# Sheet1.net
KiCad netlist of a schematic drawn in Altium Designer
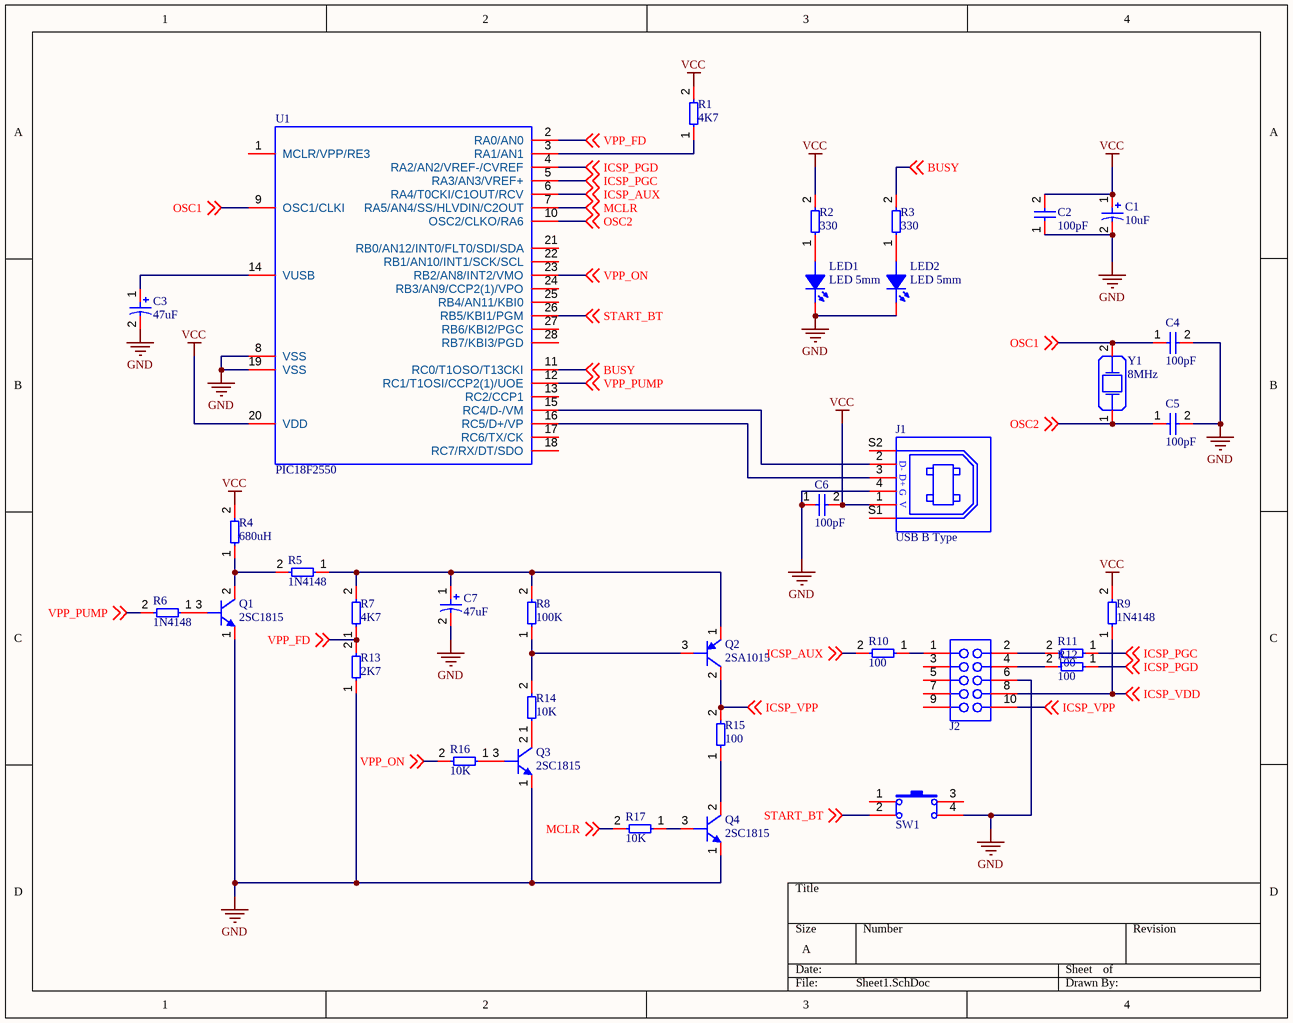
[diagram p0: Sheet1.SchDoc]

(export (version "E")
  (design (tool "Eeschema 10.0.6"))
  (components
    (comp (ref "C1")
      (value "10uF")
      (footprint "CAP_RAD_4mm")
      (libsource (lib "SMDLibrary") (part "Capacitor(Radian)"))
    )
    (comp (ref "C2")
      (value "100pF")
      (footprint "CAP_DISC_PITCH_2.54MM")
      (libsource (lib "SMDLibrary") (part "Capacitors(Disc)"))
    )
    (comp (ref "C3")
      (value "47uF")
      (footprint "CAP_RAD_4mm")
      (libsource (lib "SMDLibrary") (part "Capacitor(Radian)"))
    )
    (comp (ref "C4")
      (value "100pF")
      (footprint "CAP_DISC_PITCH_2.54MM")
      (libsource (lib "SMDLibrary") (part "Capacitors(Disc)"))
    )
    (comp (ref "C5")
      (value "100pF")
      (footprint "CAP_DISC_PITCH_2.54MM")
      (libsource (lib "SMDLibrary") (part "Capacitors(Disc)"))
    )
    (comp (ref "C6")
      (value "100pF")
      (footprint "CAP_DISC_PITCH_2.54MM")
      (libsource (lib "SMDLibrary") (part "Capacitors(Disc)"))
    )
    (comp (ref "C7")
      (value "47uF")
      (footprint "CAP_RAD_4mm")
      (libsource (lib "SMDLibrary") (part "Capacitor(Radian)"))
    )
    (comp (ref "J1")
      (value "USB B Type")
      (footprint "USB-B-TYPE")
      (libsource (lib "SMDLibrary") (part "USB B Type"))
    )
    (comp (ref "J2")
      (value "Header 5x2 TH Pitch 2.54mm")
      (footprint "Header 5x2 TH Pitch 2.54mm")
      (libsource (lib "SMDLibrary") (part "Header 5x2 TH Pitch 2.54mm"))
    )
    (comp (ref "LED1")
      (value "LED 5mm")
      (footprint "LED_5MM")
      (libsource (lib "SMDLibrary") (part "LED 5mm"))
    )
    (comp (ref "LED2")
      (value "LED 5mm")
      (footprint "LED_5MM")
      (libsource (lib "SMDLibrary") (part "LED 5mm"))
    )
    (comp (ref "Q1")
      (value "2SC1815")
      (footprint "TO-92")
      (libsource (lib "SMDLibrary") (part "2SC1815 (TO-92)"))
    )
    (comp (ref "Q2")
      (value "2SA1015")
      (footprint "TO-92")
      (libsource (lib "SMDLibrary") (part "2SA1015 (TO-92)"))
    )
    (comp (ref "Q3")
      (value "2SC1815")
      (footprint "TO-92")
      (libsource (lib "SMDLibrary") (part "2SC1815 (TO-92)"))
    )
    (comp (ref "Q4")
      (value "2SC1815")
      (footprint "TO-92")
      (libsource (lib "SMDLibrary") (part "2SC1815 (TO-92)"))
    )
    (comp (ref "R1")
      (value "4K7")
      (footprint "RES-0.25W-H-MF")
      (libsource (lib "SMDLibrary") (part "Resistors THD"))
    )
    (comp (ref "R2")
      (value "330")
      (footprint "RES-0.25W-H-MF")
      (libsource (lib "SMDLibrary") (part "Resistors THD"))
    )
    (comp (ref "R3")
      (value "330")
      (footprint "RES-0.25W-H-MF")
      (libsource (lib "SMDLibrary") (part "Resistors THD"))
    )
    (comp (ref "R4")
      (value "680uH")
      (footprint "RES-0.5W-HH-MF")
      (libsource (lib "SMDLibrary") (part "Resistors THD"))
    )
    (comp (ref "R5")
      (value "1N4148")
      (footprint "RES-0.25W-H-MF")
      (libsource (lib "") (part "Resistors THD_1"))
    )
    (comp (ref "R6")
      (value "1N4148")
      (footprint "RES-0.25W-H-MF")
      (libsource (lib "") (part "Resistors THD_1"))
    )
    (comp (ref "R7")
      (value "4K7")
      (footprint "RES-0.25W-H-MF")
      (libsource (lib "SMDLibrary") (part "Resistors THD"))
    )
    (comp (ref "R8")
      (value "100K")
      (footprint "RES-0.25W-H-MF")
      (libsource (lib "SMDLibrary") (part "Resistors THD"))
    )
    (comp (ref "R9")
      (value "1N4148")
      (footprint "RES-0.25W-H-MF")
      (libsource (lib "SMDLibrary") (part "Resistors THD"))
    )
    (comp (ref "R10")
      (value "100")
      (footprint "RES-0.25W-H-MF")
      (libsource (lib "") (part "Resistors THD_1"))
    )
    (comp (ref "R11")
      (value "100")
      (footprint "RES-0.25W-H-MF")
      (libsource (lib "") (part "Resistors THD_1"))
    )
    (comp (ref "R12")
      (value "100")
      (footprint "RES-0.25W-H-MF")
      (libsource (lib "") (part "Resistors THD_1"))
    )
    (comp (ref "R13")
      (value "2K7")
      (footprint "RES-0.25W-H-MF")
      (libsource (lib "SMDLibrary") (part "Resistors THD"))
    )
    (comp (ref "R14")
      (value "10K")
      (footprint "RES-0.25W-H-MF")
      (libsource (lib "SMDLibrary") (part "Resistors THD"))
    )
    (comp (ref "R15")
      (value "100")
      (footprint "RES-0.25W-H-MF")
      (libsource (lib "SMDLibrary") (part "Resistors THD"))
    )
    (comp (ref "R16")
      (value "10K")
      (footprint "RES-0.25W-H-MF")
      (libsource (lib "") (part "Resistors THD_1"))
    )
    (comp (ref "R17")
      (value "10K")
      (footprint "RES-0.25W-H-MF")
      (libsource (lib "") (part "Resistors THD_1"))
    )
    (comp (ref "SW1")
      (value "Button Hole")
      (footprint "BUTTON_HOLE_5.0mm")
      (libsource (lib "SMDLibrary") (part "Button Hole"))
    )
    (comp (ref "U1")
      (value "PIC18F2550")
      (footprint "DIP28_M04")
      (libsource (lib "SMDLibrary") (part "PIC18F2550"))
    )
    (comp (ref "Y1") (value "8MHz") (footprint "HC-49S") (libsource (lib "SMDLibrary") (part "Crystal")))
  )
  (nets
    (net (code "1") (name "BUSY") (class "Default")
      (node (ref "R3") (pin "2") (pinfunction "2_2") (pintype "passive"))
      (node (ref "U1") (pin "11") (pinfunction "RC0/T1OSO/T13CKI_11") (pintype "passive"))
    )
    (net (code "2") (name "GND") (class "Default")
      (node (ref "C1") (pin "2") (pinfunction "2_2") (pintype "passive"))
      (node (ref "C2") (pin "1") (pinfunction "1_1") (pintype "passive"))
      (node (ref "C3") (pin "2") (pinfunction "2_2") (pintype "passive"))
      (node (ref "C4") (pin "2") (pinfunction "2_2") (pintype "passive"))
      (node (ref "C5") (pin "2") (pinfunction "2_2") (pintype "passive"))
      (node (ref "C6") (pin "1") (pinfunction "1_1") (pintype "passive"))
      (node (ref "C7") (pin "2") (pinfunction "2_2") (pintype "passive"))
      (node (ref "J1") (pin "4") (pinfunction "4_4") (pintype "passive"))
      (node (ref "J2") (pin "6") (pinfunction "6_6") (pintype "passive"))
      (node (ref "LED1") (pin "2") (pinfunction "K_2") (pintype "passive"))
      (node (ref "LED2") (pin "2") (pinfunction "K_2") (pintype "passive"))
      (node (ref "Q1") (pin "1") (pinfunction "E_1") (pintype "passive"))
      (node (ref "Q3") (pin "1") (pinfunction "E_1") (pintype "passive"))
      (node (ref "Q4") (pin "1") (pinfunction "E_1") (pintype "passive"))
      (node (ref "R13") (pin "1") (pinfunction "1_1") (pintype "passive"))
      (node (ref "SW1") (pin "4") (pinfunction "4_4") (pintype "passive"))
      (node (ref "U1") (pin "19") (pinfunction "VSS_19") (pintype "passive"))
      (node (ref "U1") (pin "8") (pinfunction "VSS_8") (pintype "passive"))
    )
    (net (code "3") (name "ICSP_AUX") (class "Default")
      (node (ref "R10") (pin "2") (pinfunction "2_2") (pintype "passive"))
      (node (ref "U1") (pin "6") (pinfunction "RA4/T0CKI/C1OUT/RCV_6") (pintype "passive"))
    )
    (net (code "4") (name "ICSP_PGC") (class "Default")
      (node (ref "R11") (pin "1") (pinfunction "1_1") (pintype "passive"))
      (node (ref "U1") (pin "5") (pinfunction "RA3/AN3/VREF+_5") (pintype "passive"))
    )
    (net (code "5") (name "ICSP_PGD") (class "Default")
      (node (ref "R12") (pin "1") (pinfunction "1_1") (pintype "passive"))
      (node (ref "U1") (pin "4") (pinfunction "RA2/AN2/VREF-/CVREF_4") (pintype "passive"))
    )
    (net (code "6") (name "ICSP_VDD") (class "Default")
      (node (ref "J2") (pin "8") (pinfunction "8_8") (pintype "passive"))
      (node (ref "R9") (pin "1") (pinfunction "1_1") (pintype "passive"))
    )
    (net (code "7") (name "ICSP_VPP") (class "Default")
      (node (ref "J2") (pin "10") (pinfunction "10_10") (pintype "passive"))
      (node (ref "Q2") (pin "2") (pinfunction "C_2") (pintype "passive"))
      (node (ref "R15") (pin "2") (pinfunction "2_2") (pintype "passive"))
    )
    (net (code "8") (name "MCLR") (class "Default")
      (node (ref "R17") (pin "2") (pinfunction "2_2") (pintype "passive"))
      (node (ref "U1") (pin "7") (pinfunction "RA5/AN4/SS/HLVDIN/C2OUT_7") (pintype "passive"))
    )
    (net (code "9") (name "Net-(J2-Pad1)") (class "Default")
      (node (ref "J2") (pin "1") (pinfunction "1_1") (pintype "passive"))
      (node (ref "R10") (pin "1") (pinfunction "1_1") (pintype "passive"))
    )
    (net (code "10") (name "Net-(J2-Pad2)") (class "Default")
      (node (ref "J2") (pin "2") (pinfunction "2_2") (pintype "passive"))
      (node (ref "R11") (pin "2") (pinfunction "2_2") (pintype "passive"))
    )
    (net (code "11") (name "Net-(J2-Pad4)") (class "Default")
      (node (ref "J2") (pin "4") (pinfunction "4_4") (pintype "passive"))
      (node (ref "R12") (pin "2") (pinfunction "2_2") (pintype "passive"))
    )
    (net (code "12") (name "Net-(LED1-A)") (class "Default")
      (node (ref "LED1") (pin "1") (pinfunction "A_1") (pintype "passive"))
      (node (ref "R2") (pin "1") (pinfunction "1_1") (pintype "passive"))
    )
    (net (code "13") (name "Net-(LED2-A)") (class "Default")
      (node (ref "LED2") (pin "1") (pinfunction "A_1") (pintype "passive"))
      (node (ref "R3") (pin "1") (pinfunction "1_1") (pintype "passive"))
    )
    (net (code "14") (name "Net-(Q1-B)") (class "Default")
      (node (ref "Q1") (pin "3") (pinfunction "B_3") (pintype "passive"))
      (node (ref "R6") (pin "1") (pinfunction "1_1") (pintype "passive"))
    )
    (net (code "15") (name "Net-(Q1-C)") (class "Default")
      (node (ref "Q1") (pin "2") (pinfunction "C_2") (pintype "passive"))
      (node (ref "R4") (pin "1") (pinfunction "1_1") (pintype "passive"))
      (node (ref "R5") (pin "2") (pinfunction "2_2") (pintype "passive"))
    )
    (net (code "16") (name "Net-(Q2-B)") (class "Default")
      (node (ref "Q2") (pin "3") (pinfunction "B_3") (pintype "passive"))
      (node (ref "R14") (pin "2") (pinfunction "2_2") (pintype "passive"))
      (node (ref "R8") (pin "1") (pinfunction "1_1") (pintype "passive"))
    )
    (net (code "17") (name "Net-(Q2-E)") (class "Default")
      (node (ref "C7") (pin "1") (pinfunction "1_1") (pintype "passive"))
      (node (ref "Q2") (pin "1") (pinfunction "E_1") (pintype "passive"))
      (node (ref "R5") (pin "1") (pinfunction "1_1") (pintype "passive"))
      (node (ref "R7") (pin "2") (pinfunction "2_2") (pintype "passive"))
      (node (ref "R8") (pin "2") (pinfunction "2_2") (pintype "passive"))
    )
    (net (code "18") (name "Net-(Q3-B)") (class "Default")
      (node (ref "Q3") (pin "3") (pinfunction "B_3") (pintype "passive"))
      (node (ref "R16") (pin "1") (pinfunction "1_1") (pintype "passive"))
    )
    (net (code "19") (name "Net-(Q3-C)") (class "Default")
      (node (ref "Q3") (pin "2") (pinfunction "C_2") (pintype "passive"))
      (node (ref "R14") (pin "1") (pinfunction "1_1") (pintype "passive"))
    )
    (net (code "20") (name "Net-(Q4-B)") (class "Default")
      (node (ref "Q4") (pin "3") (pinfunction "B_3") (pintype "passive"))
      (node (ref "R17") (pin "1") (pinfunction "1_1") (pintype "passive"))
    )
    (net (code "21") (name "Net-(Q4-C)") (class "Default")
      (node (ref "Q4") (pin "2") (pinfunction "C_2") (pintype "passive"))
      (node (ref "R15") (pin "1") (pinfunction "1_1") (pintype "passive"))
    )
    (net (code "22") (name "Net-(U1-RA1{slash}AN1)") (class "Default")
      (node (ref "R1") (pin "1") (pinfunction "1_1") (pintype "passive"))
      (node (ref "U1") (pin "3") (pinfunction "RA1/AN1_3") (pintype "passive"))
    )
    (net (code "23") (name "Net-(U1-RC4{slash}D-{slash}VM)") (class "Default")
      (node (ref "J1") (pin "2") (pinfunction "2_2") (pintype "passive"))
      (node (ref "U1") (pin "15") (pinfunction "RC4/D-/VM_15") (pintype "passive"))
    )
    (net (code "24") (name "Net-(U1-RC5{slash}D+{slash}VP)") (class "Default")
      (node (ref "J1") (pin "3") (pinfunction "3_3") (pintype "passive"))
      (node (ref "U1") (pin "16") (pinfunction "RC5/D+/VP_16") (pintype "passive"))
    )
    (net (code "25") (name "Net-(U1-VUSB)") (class "Default")
      (node (ref "C3") (pin "1") (pinfunction "1_1") (pintype "passive"))
      (node (ref "U1") (pin "14") (pinfunction "VUSB_14") (pintype "passive"))
    )
    (net (code "26") (name "OSC1") (class "Default")
      (node (ref "C4") (pin "1") (pinfunction "1_1") (pintype "passive"))
      (node (ref "U1") (pin "9") (pinfunction "OSC1/CLKI_9") (pintype "passive"))
      (node (ref "Y1") (pin "2") (pinfunction "2_2") (pintype "passive"))
    )
    (net (code "27") (name "OSC2") (class "Default")
      (node (ref "C5") (pin "1") (pinfunction "1_1") (pintype "passive"))
      (node (ref "U1") (pin "10") (pinfunction "OSC2/CLKO/RA6_10") (pintype "passive"))
      (node (ref "Y1") (pin "1") (pinfunction "1_1") (pintype "passive"))
    )
    (net (code "28") (name "START_BT") (class "Default")
      (node (ref "SW1") (pin "2") (pinfunction "2_2") (pintype "passive"))
      (node (ref "U1") (pin "26") (pinfunction "RB5/KBI1/PGM_26") (pintype "passive"))
    )
    (net (code "29") (name "VCC") (class "Default")
      (node (ref "C1") (pin "1") (pinfunction "1_1") (pintype "passive"))
      (node (ref "C2") (pin "2") (pinfunction "2_2") (pintype "passive"))
      (node (ref "C6") (pin "2") (pinfunction "2_2") (pintype "passive"))
      (node (ref "J1") (pin "1") (pinfunction "1_1") (pintype "passive"))
      (node (ref "R1") (pin "2") (pinfunction "2_2") (pintype "passive"))
      (node (ref "R2") (pin "2") (pinfunction "2_2") (pintype "passive"))
      (node (ref "R4") (pin "2") (pinfunction "2_2") (pintype "passive"))
      (node (ref "R9") (pin "2") (pinfunction "2_2") (pintype "passive"))
      (node (ref "U1") (pin "20") (pinfunction "VDD_20") (pintype "passive"))
    )
    (net (code "30") (name "VPP_FD") (class "Default")
      (node (ref "R13") (pin "2") (pinfunction "2_2") (pintype "passive"))
      (node (ref "R7") (pin "1") (pinfunction "1_1") (pintype "passive"))
      (node (ref "U1") (pin "2") (pinfunction "RA0/AN0_2") (pintype "passive"))
    )
    (net (code "31") (name "VPP_ON") (class "Default")
      (node (ref "R16") (pin "2") (pinfunction "2_2") (pintype "passive"))
      (node (ref "U1") (pin "23") (pinfunction "RB2/AN8/INT2/VMO_23") (pintype "passive"))
    )
    (net (code "32") (name "VPP_PUMP") (class "Default")
      (node (ref "R6") (pin "2") (pinfunction "2_2") (pintype "passive"))
      (node (ref "U1") (pin "12") (pinfunction "RC1/T1OSI/CCP2(1)/UOE_12") (pintype "passive"))
    )
    (net (code "33") (name "unconnected-(J1-PadS1)") (class "Default")
      (node (ref "J1") (pin "S1") (pinfunction "S1_S1") (pintype "passive"))
    )
    (net (code "34") (name "unconnected-(J1-PadS2)") (class "Default")
      (node (ref "J1") (pin "S2") (pinfunction "S2_S2") (pintype "passive"))
    )
    (net (code "35") (name "unconnected-(J2-Pad3)") (class "Default")
      (node (ref "J2") (pin "3") (pinfunction "3_3") (pintype "passive"))
    )
    (net (code "36") (name "unconnected-(J2-Pad5)") (class "Default")
      (node (ref "J2") (pin "5") (pinfunction "5_5") (pintype "passive"))
    )
    (net (code "37") (name "unconnected-(J2-Pad7)") (class "Default")
      (node (ref "J2") (pin "7") (pinfunction "7_7") (pintype "passive"))
    )
    (net (code "38") (name "unconnected-(J2-Pad9)") (class "Default")
      (node (ref "J2") (pin "9") (pinfunction "9_9") (pintype "passive"))
    )
    (net (code "39") (name "unconnected-(SW1-Pad1)") (class "Default")
      (node (ref "SW1") (pin "1") (pinfunction "1_1") (pintype "passive"))
    )
    (net (code "40") (name "unconnected-(SW1-Pad3)") (class "Default")
      (node (ref "SW1") (pin "3") (pinfunction "3_3") (pintype "passive"))
    )
    (net (code "41") (name "unconnected-(U1-MCLR{slash}VPP{slash}RE3-Pad1)") (class "Default")
      (node (ref "U1") (pin "1") (pinfunction "MCLR/VPP/RE3_1") (pintype "passive"))
    )
    (net (code "42") (name "unconnected-(U1-RB0{slash}AN12{slash}INT0{slash}FLT0{slash}SDI{slash}SDA-Pad21)") (class "Default")
      (node (ref "U1") (pin "21") (pinfunction "RB0/AN12/INT0/FLT0/SDI/SDA_21") (pintype "passive"))
    )
    (net (code "43") (name "unconnected-(U1-RB1{slash}AN10{slash}INT1{slash}SCK{slash}SCL-Pad22)") (class "Default")
      (node (ref "U1") (pin "22") (pinfunction "RB1/AN10/INT1/SCK/SCL_22") (pintype "passive"))
    )
    (net (code "44") (name "unconnected-(U1-RB3{slash}AN9{slash}CCP2(1){slash}VPO-Pad24)") (class "Default")
      (node (ref "U1") (pin "24") (pinfunction "RB3/AN9/CCP2(1)/VPO_24") (pintype "passive"))
    )
    (net (code "45") (name "unconnected-(U1-RB4{slash}AN11{slash}KBI0-Pad25)") (class "Default")
      (node (ref "U1") (pin "25") (pinfunction "RB4/AN11/KBI0_25") (pintype "passive"))
    )
    (net (code "46") (name "unconnected-(U1-RB6{slash}KBI2{slash}PGC-Pad27)") (class "Default")
      (node (ref "U1") (pin "27") (pinfunction "RB6/KBI2/PGC_27") (pintype "passive"))
    )
    (net (code "47") (name "unconnected-(U1-RB7{slash}KBI3{slash}PGD-Pad28)") (class "Default")
      (node (ref "U1") (pin "28") (pinfunction "RB7/KBI3/PGD_28") (pintype "passive"))
    )
    (net (code "48") (name "unconnected-(U1-RC2{slash}CCP1-Pad13)") (class "Default")
      (node (ref "U1") (pin "13") (pinfunction "RC2/CCP1_13") (pintype "passive"))
    )
    (net (code "49") (name "unconnected-(U1-RC6{slash}TX{slash}CK-Pad17)") (class "Default")
      (node (ref "U1") (pin "17") (pinfunction "RC6/TX/CK_17") (pintype "passive"))
    )
    (net (code "50") (name "unconnected-(U1-RC7{slash}RX{slash}DT{slash}SDO-Pad18)") (class "Default")
      (node (ref "U1") (pin "18") (pinfunction "RC7/RX/DT/SDO_18") (pintype "passive"))
    )
  )
)
